# SCART_CONECTOR.net
KiCad netlist of a schematic drawn in EAGLE
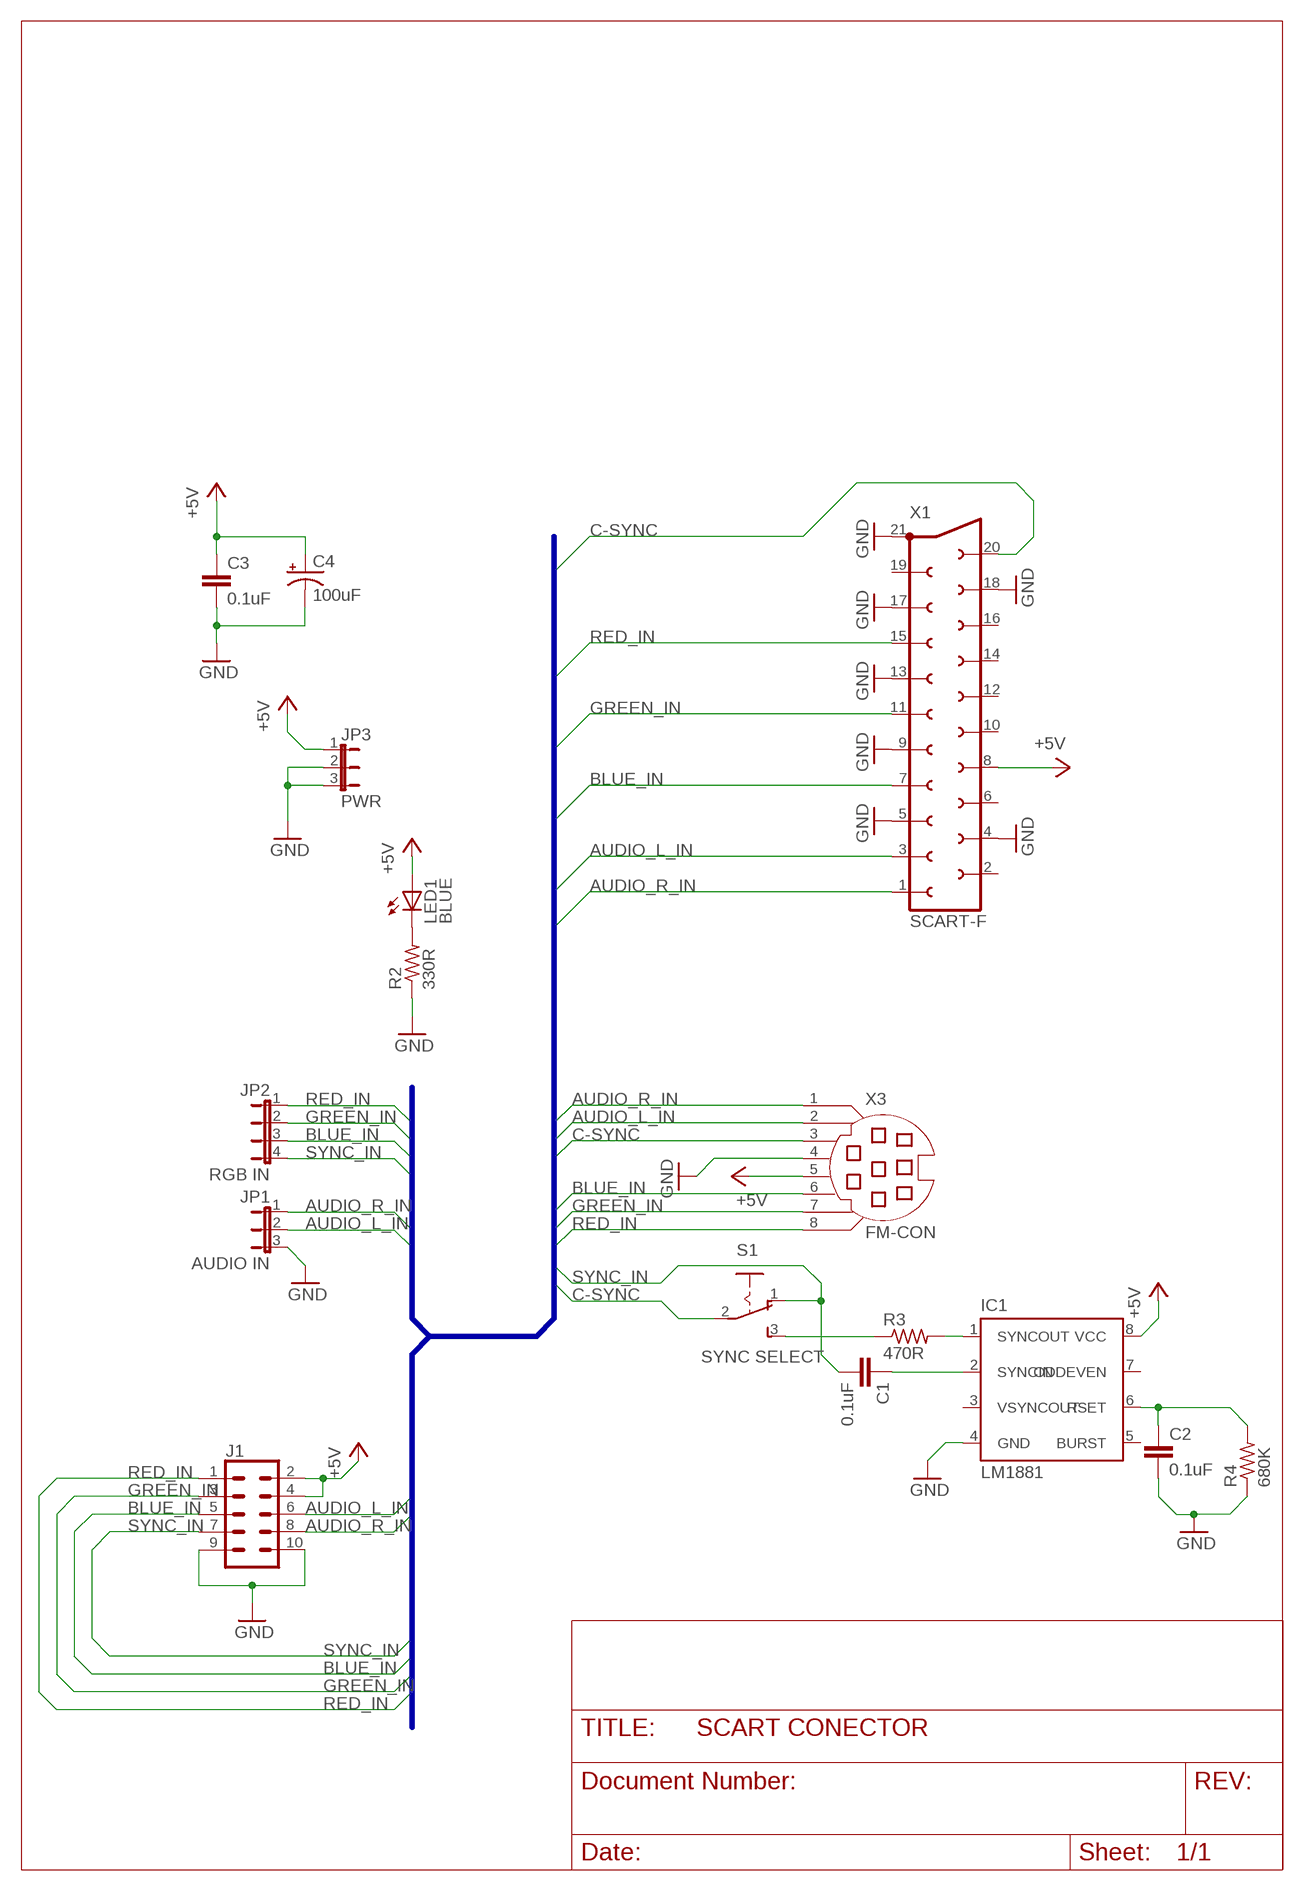
[diagram p0: schematic, sheet 1]

(export (version "E")
  (design (tool "Eeschema 10.0.6"))
  (components
    (comp (ref "C1")
      (value "0.1uF")
      (footprint "eagle-import:C7.5B3")
      (libsource (lib "eagle-import") (part "C7.5/3"))
    )
    (comp (ref "C2")
      (value "0.1uF")
      (footprint "eagle-import:C7.5B3")
      (libsource (lib "eagle-import") (part "C7.5/3"))
    )
    (comp (ref "C3")
      (value "0.1uF")
      (footprint "eagle-import:C7.5B3")
      (libsource (lib "eagle-import") (part "C7.5/3"))
    )
    (comp (ref "C4")
      (value "100uF")
      (footprint "eagle-import:E5-13")
      (libsource (lib "eagle-import") (part "CPOL-USE5-13"))
    )
    (comp (ref "IC1")
      (value "LM1881")
      (footprint "eagle-import:DIL08")
      (libsource (lib "eagle-import") (part "LM1881"))
    )
    (comp (ref "J1")
      (value "CONN_05X2SHD-NS")
      (footprint "eagle-import:2X5-SHROUDED-NS")
      (libsource (lib "eagle-import") (part "CONN_05X2SHD-NS"))
    )
    (comp (ref "JP1")
      (value "AUDIO IN")
      (footprint "eagle-import:JP2")
      (libsource (lib "eagle-import") (part "JP2E"))
    )
    (comp (ref "JP2")
      (value "RGB IN")
      (footprint "eagle-import:JP4")
      (libsource (lib "eagle-import") (part "JP4E"))
    )
    (comp (ref "JP3")
      (value "PWR")
      (footprint "eagle-import:JP2")
      (libsource (lib "eagle-import") (part "JP2E"))
    )
    (comp (ref "LED1")
      (value "BLUE")
      (footprint "eagle-import:LED5MM")
      (libsource (lib "eagle-import") (part "LED5MM"))
    )
    (comp (ref "R2")
      (value "330R")
      (footprint "eagle-import:0204_7")
      (libsource (lib "eagle-import") (part "R-US_0204/7"))
    )
    (comp (ref "R3")
      (value "470R")
      (footprint "eagle-import:0204_7")
      (libsource (lib "eagle-import") (part "R-US_0204/7"))
    )
    (comp (ref "R4")
      (value "680K")
      (footprint "eagle-import:0204_7")
      (libsource (lib "eagle-import") (part "R-US_0204/7"))
    )
    (comp (ref "S1")
      (value "SYNC SELECT")
      (footprint "eagle-import:255SB")
      (libsource (lib "eagle-import") (part "255SB"))
    )
    (comp (ref "X1")
      (value "SCART-F")
      (footprint "eagle-import:SCART-F")
      (libsource (lib "eagle-import") (part "SCART-F"))
    )
    (comp (ref "X3")
      (value "FM-CON")
      (footprint "eagle-import:MDIN08SS")
      (libsource (lib "eagle-import") (part "MD08SS"))
    )
  )
  (nets
    (net (code "1") (name "+5V") (class "Default")
      (node (ref "C3") (pin "1") (pinfunction "1_1") (pintype "passive"))
      (node (ref "C4") (pin "+") (pinfunction "+_+") (pintype "passive"))
      (node (ref "IC1") (pin "8") (pinfunction "VCC_8") (pintype "power_in"))
      (node (ref "J1") (pin "2") (pinfunction "2_2") (pintype "passive"))
      (node (ref "J1") (pin "4") (pinfunction "4_4") (pintype "passive"))
      (node (ref "JP3") (pin "1") (pinfunction "1_1") (pintype "passive"))
      (node (ref "LED1") (pin "A") (pinfunction "A_A") (pintype "passive"))
      (node (ref "X1") (pin "8") (pinfunction "8_8") (pintype "passive"))
      (node (ref "X3") (pin "5") (pinfunction "5_5") (pintype "passive"))
    )
    (net (code "2") (name "/AUDIO_L_IN") (class "Default")
      (node (ref "J1") (pin "6") (pinfunction "6_6") (pintype "passive"))
      (node (ref "JP1") (pin "2") (pinfunction "2_2") (pintype "passive"))
      (node (ref "X1") (pin "3") (pinfunction "3_3") (pintype "passive"))
      (node (ref "X3") (pin "2") (pinfunction "2_2") (pintype "passive"))
    )
    (net (code "3") (name "/AUDIO_R_IN") (class "Default")
      (node (ref "J1") (pin "8") (pinfunction "8_8") (pintype "passive"))
      (node (ref "JP1") (pin "1") (pinfunction "1_1") (pintype "passive"))
      (node (ref "X1") (pin "1") (pinfunction "1_1") (pintype "passive"))
      (node (ref "X3") (pin "1") (pinfunction "1_1") (pintype "passive"))
    )
    (net (code "4") (name "/BLUE_IN") (class "Default")
      (node (ref "J1") (pin "5") (pinfunction "5_5") (pintype "passive"))
      (node (ref "JP2") (pin "3") (pinfunction "3_3") (pintype "passive"))
      (node (ref "X1") (pin "7") (pinfunction "7_7") (pintype "passive"))
      (node (ref "X3") (pin "6") (pinfunction "6_6") (pintype "passive"))
    )
    (net (code "5") (name "/C-SYNC") (class "Default")
      (node (ref "S1") (pin "2") (pinfunction "P_2") (pintype "passive"))
      (node (ref "X1") (pin "20") (pinfunction "20_20") (pintype "passive"))
      (node (ref "X3") (pin "3") (pinfunction "3_3") (pintype "passive"))
    )
    (net (code "6") (name "/GREEN_IN") (class "Default")
      (node (ref "J1") (pin "3") (pinfunction "3_3") (pintype "passive"))
      (node (ref "JP2") (pin "2") (pinfunction "2_2") (pintype "passive"))
      (node (ref "X1") (pin "11") (pinfunction "11_11") (pintype "passive"))
      (node (ref "X3") (pin "7") (pinfunction "7_7") (pintype "passive"))
    )
    (net (code "7") (name "/RED_IN") (class "Default")
      (node (ref "J1") (pin "1") (pinfunction "1_1") (pintype "passive"))
      (node (ref "JP2") (pin "1") (pinfunction "1_1") (pintype "passive"))
      (node (ref "X1") (pin "15") (pinfunction "15_15") (pintype "passive"))
      (node (ref "X3") (pin "8") (pinfunction "8_8") (pintype "passive"))
    )
    (net (code "8") (name "/SYNC_IN") (class "Default")
      (node (ref "C1") (pin "2") (pinfunction "2_2") (pintype "passive"))
      (node (ref "J1") (pin "7") (pinfunction "7_7") (pintype "passive"))
      (node (ref "JP2") (pin "4") (pinfunction "4_4") (pintype "passive"))
      (node (ref "S1") (pin "1") (pinfunction "O_1") (pintype "passive"))
    )
    (net (code "9") (name "GND") (class "Default")
      (node (ref "C2") (pin "2") (pinfunction "2_2") (pintype "passive"))
      (node (ref "C3") (pin "2") (pinfunction "2_2") (pintype "passive"))
      (node (ref "C4") (pin "-") (pinfunction "-_-") (pintype "passive"))
      (node (ref "IC1") (pin "4") (pinfunction "GND_4") (pintype "power_in"))
      (node (ref "J1") (pin "10") (pinfunction "10_10") (pintype "passive"))
      (node (ref "J1") (pin "9") (pinfunction "9_9") (pintype "passive"))
      (node (ref "JP1") (pin "3") (pinfunction "3_3") (pintype "passive"))
      (node (ref "JP3") (pin "2") (pinfunction "2_2") (pintype "passive"))
      (node (ref "JP3") (pin "3") (pinfunction "3_3") (pintype "passive"))
      (node (ref "R2") (pin "1") (pinfunction "1_1") (pintype "passive"))
      (node (ref "R4") (pin "1") (pinfunction "1_1") (pintype "passive"))
      (node (ref "X1") (pin "13") (pinfunction "13_13") (pintype "passive"))
      (node (ref "X1") (pin "17") (pinfunction "17_17") (pintype "passive"))
      (node (ref "X1") (pin "18") (pinfunction "18_18") (pintype "passive"))
      (node (ref "X1") (pin "21") (pinfunction "21_21") (pintype "passive"))
      (node (ref "X1") (pin "4") (pinfunction "4_4") (pintype "passive"))
      (node (ref "X1") (pin "5") (pinfunction "5_5") (pintype "passive"))
      (node (ref "X1") (pin "9") (pinfunction "9_9") (pintype "passive"))
      (node (ref "X3") (pin "4") (pinfunction "4_4") (pintype "passive"))
    )
    (net (code "10") (name "Net-(IC1-RSET)") (class "Default")
      (node (ref "C2") (pin "1") (pinfunction "1_1") (pintype "passive"))
      (node (ref "IC1") (pin "6") (pinfunction "RSET_6") (pintype "output"))
      (node (ref "R4") (pin "2") (pinfunction "2_2") (pintype "passive"))
    )
    (net (code "11") (name "Net-(IC1-SYNCIN)") (class "Default")
      (node (ref "C1") (pin "1") (pinfunction "1_1") (pintype "passive"))
      (node (ref "IC1") (pin "2") (pinfunction "SYNCIN_2") (pintype "input"))
    )
    (net (code "12") (name "Net-(IC1-SYNCOUT)") (class "Default")
      (node (ref "IC1") (pin "1") (pinfunction "SYNCOUT_1") (pintype "output"))
      (node (ref "R3") (pin "2") (pinfunction "2_2") (pintype "passive"))
    )
    (net (code "13") (name "Net-(LED1-C)") (class "Default")
      (node (ref "LED1") (pin "K") (pinfunction "C_K") (pintype "passive"))
      (node (ref "R2") (pin "2") (pinfunction "2_2") (pintype "passive"))
    )
    (net (code "14") (name "Net-(S1-S)") (class "Default")
      (node (ref "R3") (pin "1") (pinfunction "1_1") (pintype "passive"))
      (node (ref "S1") (pin "3") (pinfunction "S_3") (pintype "passive"))
    )
    (net (code "15") (name "unconnected-(IC1-BURST-Pad5)") (class "Default")
      (node (ref "IC1") (pin "5") (pinfunction "BURST_5") (pintype "output"))
    )
    (net (code "16") (name "unconnected-(IC1-ODDEVEN-Pad7)") (class "Default")
      (node (ref "IC1") (pin "7") (pinfunction "ODDEVEN_7") (pintype "output"))
    )
    (net (code "17") (name "unconnected-(IC1-VSYNCOUT-Pad3)") (class "Default")
      (node (ref "IC1") (pin "3") (pinfunction "VSYNCOUT_3") (pintype "output"))
    )
    (net (code "18") (name "unconnected-(X1-Pad2)") (class "Default")
      (node (ref "X1") (pin "2") (pinfunction "2_2") (pintype "passive"))
    )
    (net (code "19") (name "unconnected-(X1-Pad6)") (class "Default")
      (node (ref "X1") (pin "6") (pinfunction "6_6") (pintype "passive"))
    )
    (net (code "20") (name "unconnected-(X1-Pad10)") (class "Default")
      (node (ref "X1") (pin "10") (pinfunction "10_10") (pintype "passive"))
    )
    (net (code "21") (name "unconnected-(X1-Pad12)") (class "Default")
      (node (ref "X1") (pin "12") (pinfunction "12_12") (pintype "passive"))
    )
    (net (code "22") (name "unconnected-(X1-Pad14)") (class "Default")
      (node (ref "X1") (pin "14") (pinfunction "14_14") (pintype "passive"))
    )
    (net (code "23") (name "unconnected-(X1-Pad16)") (class "Default")
      (node (ref "X1") (pin "16") (pinfunction "16_16") (pintype "passive"))
    )
    (net (code "24") (name "unconnected-(X1-Pad19)") (class "Default")
      (node (ref "X1") (pin "19") (pinfunction "19_19") (pintype "passive"))
    )
  )
)
